# 04_LEDs.net
KiCad netlist of a schematic drawn in Altium Designer
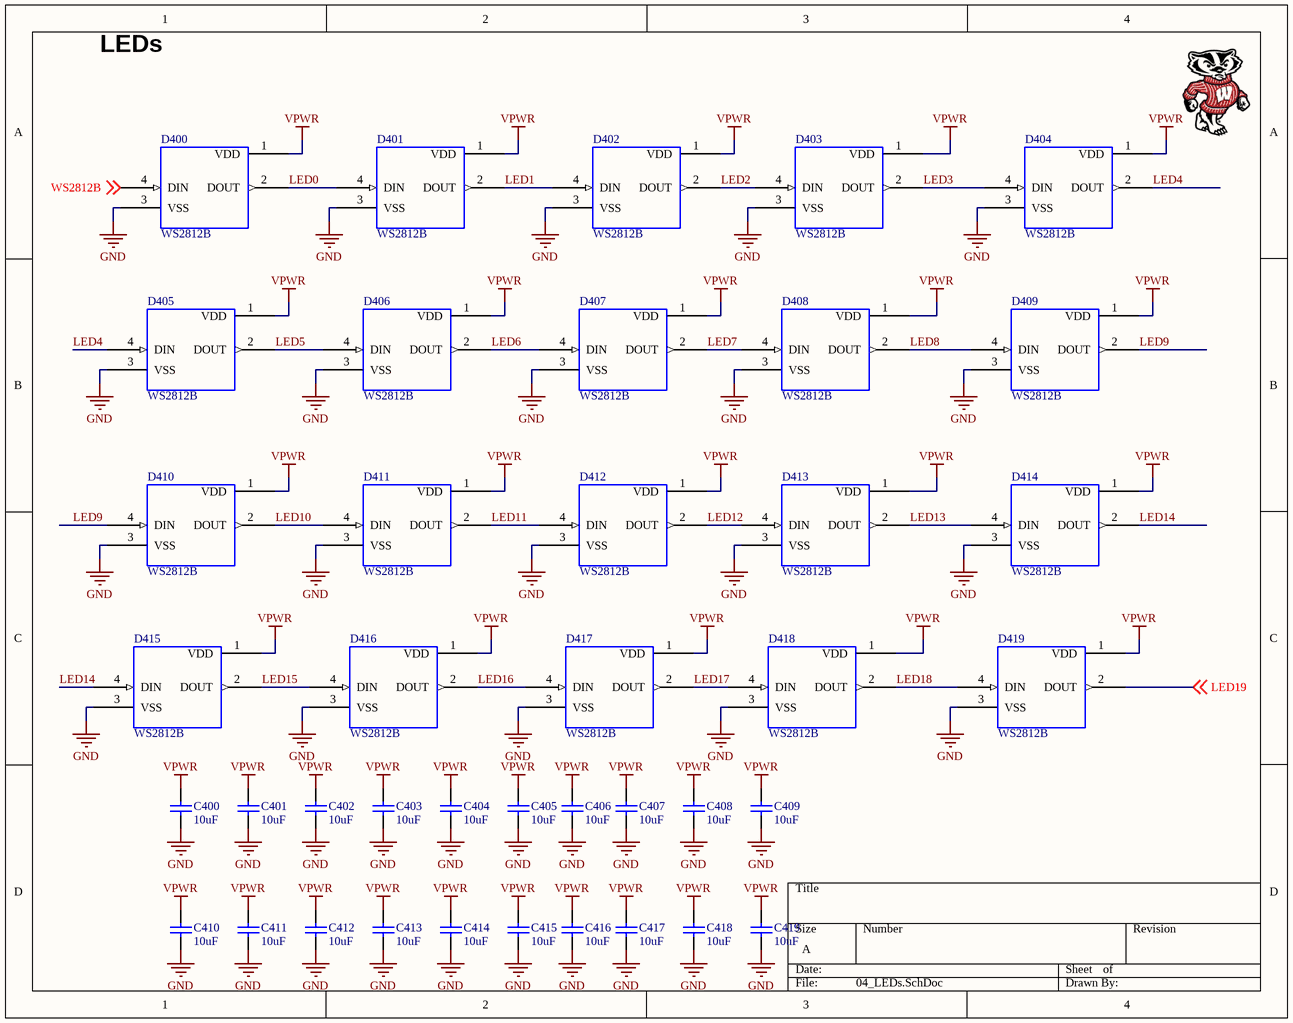
[diagram p0: 04_LEDs.SchDoc]

(export (version "E")
  (design (tool "Eeschema 10.0.6"))
  (components
    (comp (ref "C400")
      (value "10uF")
      (footprint "CAP_0805")
      (description "CAP CER 10UF 16V X7R 0805")
      (fields
        (field (name "MANUFACTURER") "Samsung")
        (field (name "MANUFACTURER PART NUMBER") "CL21A106KPCLQNC")
        (field (name "CAPACITANCE") "10uF")
      )
      (libsource (lib "ece315-2018-fall") (part "CAP_0805_U_010.00"))
    )
    (comp (ref "C401")
      (value "10uF")
      (footprint "CAP_0805")
      (description "CAP CER 10UF 16V X7R 0805")
      (fields
        (field (name "MANUFACTURER") "Samsung")
        (field (name "MANUFACTURER PART NUMBER") "CL21A106KPCLQNC")
        (field (name "CAPACITANCE") "10uF")
      )
      (libsource (lib "ece315-2018-fall") (part "CAP_0805_U_010.00"))
    )
    (comp (ref "C402")
      (value "10uF")
      (footprint "CAP_0805")
      (description "CAP CER 10UF 16V X7R 0805")
      (fields
        (field (name "MANUFACTURER") "Samsung")
        (field (name "MANUFACTURER PART NUMBER") "CL21A106KPCLQNC")
        (field (name "CAPACITANCE") "10uF")
      )
      (libsource (lib "ece315-2018-fall") (part "CAP_0805_U_010.00"))
    )
    (comp (ref "C403")
      (value "10uF")
      (footprint "CAP_0805")
      (description "CAP CER 10UF 16V X7R 0805")
      (fields
        (field (name "MANUFACTURER") "Samsung")
        (field (name "MANUFACTURER PART NUMBER") "CL21A106KPCLQNC")
        (field (name "CAPACITANCE") "10uF")
      )
      (libsource (lib "ece315-2018-fall") (part "CAP_0805_U_010.00"))
    )
    (comp (ref "C404")
      (value "10uF")
      (footprint "CAP_0805")
      (description "CAP CER 10UF 16V X7R 0805")
      (fields
        (field (name "MANUFACTURER") "Samsung")
        (field (name "MANUFACTURER PART NUMBER") "CL21A106KPCLQNC")
        (field (name "CAPACITANCE") "10uF")
      )
      (libsource (lib "ece315-2018-fall") (part "CAP_0805_U_010.00"))
    )
    (comp (ref "C405")
      (value "10uF")
      (footprint "CAP_0805")
      (description "CAP CER 10UF 16V X7R 0805")
      (fields
        (field (name "MANUFACTURER") "Samsung")
        (field (name "MANUFACTURER PART NUMBER") "CL21A106KPCLQNC")
        (field (name "CAPACITANCE") "10uF")
      )
      (libsource (lib "ece315-2018-fall") (part "CAP_0805_U_010.00"))
    )
    (comp (ref "C406")
      (value "10uF")
      (footprint "CAP_0805")
      (description "CAP CER 10UF 16V X7R 0805")
      (fields
        (field (name "MANUFACTURER") "Samsung")
        (field (name "MANUFACTURER PART NUMBER") "CL21A106KPCLQNC")
        (field (name "CAPACITANCE") "10uF")
      )
      (libsource (lib "ece315-2018-fall") (part "CAP_0805_U_010.00"))
    )
    (comp (ref "C407")
      (value "10uF")
      (footprint "CAP_0805")
      (description "CAP CER 10UF 16V X7R 0805")
      (fields
        (field (name "MANUFACTURER") "Samsung")
        (field (name "MANUFACTURER PART NUMBER") "CL21A106KPCLQNC")
        (field (name "CAPACITANCE") "10uF")
      )
      (libsource (lib "ece315-2018-fall") (part "CAP_0805_U_010.00"))
    )
    (comp (ref "C408")
      (value "10uF")
      (footprint "CAP_0805")
      (description "CAP CER 10UF 16V X7R 0805")
      (fields
        (field (name "MANUFACTURER") "Samsung")
        (field (name "MANUFACTURER PART NUMBER") "CL21A106KPCLQNC")
        (field (name "CAPACITANCE") "10uF")
      )
      (libsource (lib "ece315-2018-fall") (part "CAP_0805_U_010.00"))
    )
    (comp (ref "C409")
      (value "10uF")
      (footprint "CAP_0805")
      (description "CAP CER 10UF 16V X7R 0805")
      (fields
        (field (name "MANUFACTURER") "Samsung")
        (field (name "MANUFACTURER PART NUMBER") "CL21A106KPCLQNC")
        (field (name "CAPACITANCE") "10uF")
      )
      (libsource (lib "ece315-2018-fall") (part "CAP_0805_U_010.00"))
    )
    (comp (ref "C410")
      (value "10uF")
      (footprint "CAP_0805")
      (description "CAP CER 10UF 16V X7R 0805")
      (fields
        (field (name "MANUFACTURER") "Samsung")
        (field (name "MANUFACTURER PART NUMBER") "CL21A106KPCLQNC")
        (field (name "CAPACITANCE") "10uF")
      )
      (libsource (lib "ece315-2018-fall") (part "CAP_0805_U_010.00"))
    )
    (comp (ref "C411")
      (value "10uF")
      (footprint "CAP_0805")
      (description "CAP CER 10UF 16V X7R 0805")
      (fields
        (field (name "MANUFACTURER") "Samsung")
        (field (name "MANUFACTURER PART NUMBER") "CL21A106KPCLQNC")
        (field (name "CAPACITANCE") "10uF")
      )
      (libsource (lib "ece315-2018-fall") (part "CAP_0805_U_010.00"))
    )
    (comp (ref "C412")
      (value "10uF")
      (footprint "CAP_0805")
      (description "CAP CER 10UF 16V X7R 0805")
      (fields
        (field (name "MANUFACTURER") "Samsung")
        (field (name "MANUFACTURER PART NUMBER") "CL21A106KPCLQNC")
        (field (name "CAPACITANCE") "10uF")
      )
      (libsource (lib "ece315-2018-fall") (part "CAP_0805_U_010.00"))
    )
    (comp (ref "C413")
      (value "10uF")
      (footprint "CAP_0805")
      (description "CAP CER 10UF 16V X7R 0805")
      (fields
        (field (name "MANUFACTURER") "Samsung")
        (field (name "MANUFACTURER PART NUMBER") "CL21A106KPCLQNC")
        (field (name "CAPACITANCE") "10uF")
      )
      (libsource (lib "ece315-2018-fall") (part "CAP_0805_U_010.00"))
    )
    (comp (ref "C414")
      (value "10uF")
      (footprint "CAP_0805")
      (description "CAP CER 10UF 16V X7R 0805")
      (fields
        (field (name "MANUFACTURER") "Samsung")
        (field (name "MANUFACTURER PART NUMBER") "CL21A106KPCLQNC")
        (field (name "CAPACITANCE") "10uF")
      )
      (libsource (lib "ece315-2018-fall") (part "CAP_0805_U_010.00"))
    )
    (comp (ref "C415")
      (value "10uF")
      (footprint "CAP_0805")
      (description "CAP CER 10UF 16V X7R 0805")
      (fields
        (field (name "MANUFACTURER") "Samsung")
        (field (name "MANUFACTURER PART NUMBER") "CL21A106KPCLQNC")
        (field (name "CAPACITANCE") "10uF")
      )
      (libsource (lib "ece315-2018-fall") (part "CAP_0805_U_010.00"))
    )
    (comp (ref "C416")
      (value "10uF")
      (footprint "CAP_0805")
      (description "CAP CER 10UF 16V X7R 0805")
      (fields
        (field (name "MANUFACTURER") "Samsung")
        (field (name "MANUFACTURER PART NUMBER") "CL21A106KPCLQNC")
        (field (name "CAPACITANCE") "10uF")
      )
      (libsource (lib "ece315-2018-fall") (part "CAP_0805_U_010.00"))
    )
    (comp (ref "C417")
      (value "10uF")
      (footprint "CAP_0805")
      (description "CAP CER 10UF 16V X7R 0805")
      (fields
        (field (name "MANUFACTURER") "Samsung")
        (field (name "MANUFACTURER PART NUMBER") "CL21A106KPCLQNC")
        (field (name "CAPACITANCE") "10uF")
      )
      (libsource (lib "ece315-2018-fall") (part "CAP_0805_U_010.00"))
    )
    (comp (ref "C418")
      (value "10uF")
      (footprint "CAP_0805")
      (description "CAP CER 10UF 16V X7R 0805")
      (fields
        (field (name "MANUFACTURER") "Samsung")
        (field (name "MANUFACTURER PART NUMBER") "CL21A106KPCLQNC")
        (field (name "CAPACITANCE") "10uF")
      )
      (libsource (lib "ece315-2018-fall") (part "CAP_0805_U_010.00"))
    )
    (comp (ref "C419")
      (value "10uF")
      (footprint "CAP_0805")
      (description "CAP CER 10UF 16V X7R 0805")
      (fields
        (field (name "MANUFACTURER") "Samsung")
        (field (name "MANUFACTURER PART NUMBER") "CL21A106KPCLQNC")
        (field (name "CAPACITANCE") "10uF")
      )
      (libsource (lib "ece315-2018-fall") (part "CAP_0805_U_010.00"))
    )
    (comp (ref "D400")
      (value "WS2812B")
      (footprint "WS2812B")
      (description "LED RGB WS2812B")
      (fields (field (name "MANUFACTURER PART NUMBER") "EBAY"))
      (libsource (lib "LEDs") (part "WS2812B"))
    )
    (comp (ref "D401")
      (value "WS2812B")
      (footprint "WS2812B")
      (description "LED RGB WS2812B")
      (fields (field (name "MANUFACTURER PART NUMBER") "EBAY"))
      (libsource (lib "LEDs") (part "WS2812B"))
    )
    (comp (ref "D402")
      (value "WS2812B")
      (footprint "WS2812B")
      (description "LED RGB WS2812B")
      (fields (field (name "MANUFACTURER PART NUMBER") "EBAY"))
      (libsource (lib "LEDs") (part "WS2812B"))
    )
    (comp (ref "D403")
      (value "WS2812B")
      (footprint "WS2812B")
      (description "LED RGB WS2812B")
      (fields (field (name "MANUFACTURER PART NUMBER") "EBAY"))
      (libsource (lib "LEDs") (part "WS2812B"))
    )
    (comp (ref "D404")
      (value "WS2812B")
      (footprint "WS2812B")
      (description "LED RGB WS2812B")
      (fields (field (name "MANUFACTURER PART NUMBER") "EBAY"))
      (libsource (lib "LEDs") (part "WS2812B"))
    )
    (comp (ref "D405")
      (value "WS2812B")
      (footprint "WS2812B")
      (description "LED RGB WS2812B")
      (fields (field (name "MANUFACTURER PART NUMBER") "EBAY"))
      (libsource (lib "LEDs") (part "WS2812B"))
    )
    (comp (ref "D406")
      (value "WS2812B")
      (footprint "WS2812B")
      (description "LED RGB WS2812B")
      (fields (field (name "MANUFACTURER PART NUMBER") "EBAY"))
      (libsource (lib "LEDs") (part "WS2812B"))
    )
    (comp (ref "D407")
      (value "WS2812B")
      (footprint "WS2812B")
      (description "LED RGB WS2812B")
      (fields (field (name "MANUFACTURER PART NUMBER") "EBAY"))
      (libsource (lib "LEDs") (part "WS2812B"))
    )
    (comp (ref "D408")
      (value "WS2812B")
      (footprint "WS2812B")
      (description "LED RGB WS2812B")
      (fields (field (name "MANUFACTURER PART NUMBER") "EBAY"))
      (libsource (lib "LEDs") (part "WS2812B"))
    )
    (comp (ref "D409")
      (value "WS2812B")
      (footprint "WS2812B")
      (description "LED RGB WS2812B")
      (fields (field (name "MANUFACTURER PART NUMBER") "EBAY"))
      (libsource (lib "LEDs") (part "WS2812B"))
    )
    (comp (ref "D410")
      (value "WS2812B")
      (footprint "WS2812B")
      (description "LED RGB WS2812B")
      (fields (field (name "MANUFACTURER PART NUMBER") "EBAY"))
      (libsource (lib "LEDs") (part "WS2812B"))
    )
    (comp (ref "D411")
      (value "WS2812B")
      (footprint "WS2812B")
      (description "LED RGB WS2812B")
      (fields (field (name "MANUFACTURER PART NUMBER") "EBAY"))
      (libsource (lib "LEDs") (part "WS2812B"))
    )
    (comp (ref "D412")
      (value "WS2812B")
      (footprint "WS2812B")
      (description "LED RGB WS2812B")
      (fields (field (name "MANUFACTURER PART NUMBER") "EBAY"))
      (libsource (lib "LEDs") (part "WS2812B"))
    )
    (comp (ref "D413")
      (value "WS2812B")
      (footprint "WS2812B")
      (description "LED RGB WS2812B")
      (fields (field (name "MANUFACTURER PART NUMBER") "EBAY"))
      (libsource (lib "LEDs") (part "WS2812B"))
    )
    (comp (ref "D414")
      (value "WS2812B")
      (footprint "WS2812B")
      (description "LED RGB WS2812B")
      (fields (field (name "MANUFACTURER PART NUMBER") "EBAY"))
      (libsource (lib "LEDs") (part "WS2812B"))
    )
    (comp (ref "D415")
      (value "WS2812B")
      (footprint "WS2812B")
      (description "LED RGB WS2812B")
      (fields (field (name "MANUFACTURER PART NUMBER") "EBAY"))
      (libsource (lib "LEDs") (part "WS2812B"))
    )
    (comp (ref "D416")
      (value "WS2812B")
      (footprint "WS2812B")
      (description "LED RGB WS2812B")
      (fields (field (name "MANUFACTURER PART NUMBER") "EBAY"))
      (libsource (lib "LEDs") (part "WS2812B"))
    )
    (comp (ref "D417")
      (value "WS2812B")
      (footprint "WS2812B")
      (description "LED RGB WS2812B")
      (fields (field (name "MANUFACTURER PART NUMBER") "EBAY"))
      (libsource (lib "LEDs") (part "WS2812B"))
    )
    (comp (ref "D418")
      (value "WS2812B")
      (footprint "WS2812B")
      (description "LED RGB WS2812B")
      (fields (field (name "MANUFACTURER PART NUMBER") "EBAY"))
      (libsource (lib "LEDs") (part "WS2812B"))
    )
    (comp (ref "D419")
      (value "WS2812B")
      (footprint "WS2812B")
      (description "LED RGB WS2812B")
      (fields (field (name "MANUFACTURER PART NUMBER") "EBAY"))
      (libsource (lib "LEDs") (part "WS2812B"))
    )
  )
  (nets
    (net (code "1") (name "/LED0") (class "Default")
      (node (ref "D400") (pin "2") (pinfunction "DOUT_2") (pintype "output"))
      (node (ref "D401") (pin "4") (pinfunction "DIN_4") (pintype "input"))
    )
    (net (code "2") (name "/LED1") (class "Default")
      (node (ref "D401") (pin "2") (pinfunction "DOUT_2") (pintype "output"))
      (node (ref "D402") (pin "4") (pinfunction "DIN_4") (pintype "input"))
    )
    (net (code "3") (name "/LED2") (class "Default")
      (node (ref "D402") (pin "2") (pinfunction "DOUT_2") (pintype "output"))
      (node (ref "D403") (pin "4") (pinfunction "DIN_4") (pintype "input"))
    )
    (net (code "4") (name "/LED3") (class "Default")
      (node (ref "D403") (pin "2") (pinfunction "DOUT_2") (pintype "output"))
      (node (ref "D404") (pin "4") (pinfunction "DIN_4") (pintype "input"))
    )
    (net (code "5") (name "/LED4") (class "Default")
      (node (ref "D404") (pin "2") (pinfunction "DOUT_2") (pintype "output"))
      (node (ref "D405") (pin "4") (pinfunction "DIN_4") (pintype "input"))
    )
    (net (code "6") (name "/LED5") (class "Default")
      (node (ref "D405") (pin "2") (pinfunction "DOUT_2") (pintype "output"))
      (node (ref "D406") (pin "4") (pinfunction "DIN_4") (pintype "input"))
    )
    (net (code "7") (name "/LED6") (class "Default")
      (node (ref "D406") (pin "2") (pinfunction "DOUT_2") (pintype "output"))
      (node (ref "D407") (pin "4") (pinfunction "DIN_4") (pintype "input"))
    )
    (net (code "8") (name "/LED7") (class "Default")
      (node (ref "D407") (pin "2") (pinfunction "DOUT_2") (pintype "output"))
      (node (ref "D408") (pin "4") (pinfunction "DIN_4") (pintype "input"))
    )
    (net (code "9") (name "/LED8") (class "Default")
      (node (ref "D408") (pin "2") (pinfunction "DOUT_2") (pintype "output"))
      (node (ref "D409") (pin "4") (pinfunction "DIN_4") (pintype "input"))
    )
    (net (code "10") (name "/LED9") (class "Default")
      (node (ref "D409") (pin "2") (pinfunction "DOUT_2") (pintype "output"))
      (node (ref "D410") (pin "4") (pinfunction "DIN_4") (pintype "input"))
    )
    (net (code "11") (name "/LED10") (class "Default")
      (node (ref "D410") (pin "2") (pinfunction "DOUT_2") (pintype "output"))
      (node (ref "D411") (pin "4") (pinfunction "DIN_4") (pintype "input"))
    )
    (net (code "12") (name "/LED11") (class "Default")
      (node (ref "D411") (pin "2") (pinfunction "DOUT_2") (pintype "output"))
      (node (ref "D412") (pin "4") (pinfunction "DIN_4") (pintype "input"))
    )
    (net (code "13") (name "/LED12") (class "Default")
      (node (ref "D412") (pin "2") (pinfunction "DOUT_2") (pintype "output"))
      (node (ref "D413") (pin "4") (pinfunction "DIN_4") (pintype "input"))
    )
    (net (code "14") (name "/LED13") (class "Default")
      (node (ref "D413") (pin "2") (pinfunction "DOUT_2") (pintype "output"))
      (node (ref "D414") (pin "4") (pinfunction "DIN_4") (pintype "input"))
    )
    (net (code "15") (name "/LED14") (class "Default")
      (node (ref "D414") (pin "2") (pinfunction "DOUT_2") (pintype "output"))
      (node (ref "D415") (pin "4") (pinfunction "DIN_4") (pintype "input"))
    )
    (net (code "16") (name "/LED15") (class "Default")
      (node (ref "D415") (pin "2") (pinfunction "DOUT_2") (pintype "output"))
      (node (ref "D416") (pin "4") (pinfunction "DIN_4") (pintype "input"))
    )
    (net (code "17") (name "/LED16") (class "Default")
      (node (ref "D416") (pin "2") (pinfunction "DOUT_2") (pintype "output"))
      (node (ref "D417") (pin "4") (pinfunction "DIN_4") (pintype "input"))
    )
    (net (code "18") (name "/LED17") (class "Default")
      (node (ref "D417") (pin "2") (pinfunction "DOUT_2") (pintype "output"))
      (node (ref "D418") (pin "4") (pinfunction "DIN_4") (pintype "input"))
    )
    (net (code "19") (name "/LED18") (class "Default")
      (node (ref "D418") (pin "2") (pinfunction "DOUT_2") (pintype "output"))
      (node (ref "D419") (pin "4") (pinfunction "DIN_4") (pintype "input"))
    )
    (net (code "20") (name "GND") (class "Default")
      (node (ref "C400") (pin "1") (pinfunction "1_1") (pintype "passive"))
      (node (ref "C401") (pin "1") (pinfunction "1_1") (pintype "passive"))
      (node (ref "C402") (pin "1") (pinfunction "1_1") (pintype "passive"))
      (node (ref "C403") (pin "1") (pinfunction "1_1") (pintype "passive"))
      (node (ref "C404") (pin "1") (pinfunction "1_1") (pintype "passive"))
      (node (ref "C405") (pin "1") (pinfunction "1_1") (pintype "passive"))
      (node (ref "C406") (pin "1") (pinfunction "1_1") (pintype "passive"))
      (node (ref "C407") (pin "1") (pinfunction "1_1") (pintype "passive"))
      (node (ref "C408") (pin "1") (pinfunction "1_1") (pintype "passive"))
      (node (ref "C409") (pin "1") (pinfunction "1_1") (pintype "passive"))
      (node (ref "C410") (pin "1") (pinfunction "1_1") (pintype "passive"))
      (node (ref "C411") (pin "1") (pinfunction "1_1") (pintype "passive"))
      (node (ref "C412") (pin "1") (pinfunction "1_1") (pintype "passive"))
      (node (ref "C413") (pin "1") (pinfunction "1_1") (pintype "passive"))
      (node (ref "C414") (pin "1") (pinfunction "1_1") (pintype "passive"))
      (node (ref "C415") (pin "1") (pinfunction "1_1") (pintype "passive"))
      (node (ref "C416") (pin "1") (pinfunction "1_1") (pintype "passive"))
      (node (ref "C417") (pin "1") (pinfunction "1_1") (pintype "passive"))
      (node (ref "C418") (pin "1") (pinfunction "1_1") (pintype "passive"))
      (node (ref "C419") (pin "1") (pinfunction "1_1") (pintype "passive"))
      (node (ref "D400") (pin "3") (pinfunction "VSS_3") (pintype "power_in"))
      (node (ref "D401") (pin "3") (pinfunction "VSS_3") (pintype "power_in"))
      (node (ref "D402") (pin "3") (pinfunction "VSS_3") (pintype "power_in"))
      (node (ref "D403") (pin "3") (pinfunction "VSS_3") (pintype "power_in"))
      (node (ref "D404") (pin "3") (pinfunction "VSS_3") (pintype "power_in"))
      (node (ref "D405") (pin "3") (pinfunction "VSS_3") (pintype "power_in"))
      (node (ref "D406") (pin "3") (pinfunction "VSS_3") (pintype "power_in"))
      (node (ref "D407") (pin "3") (pinfunction "VSS_3") (pintype "power_in"))
      (node (ref "D408") (pin "3") (pinfunction "VSS_3") (pintype "power_in"))
      (node (ref "D409") (pin "3") (pinfunction "VSS_3") (pintype "power_in"))
      (node (ref "D410") (pin "3") (pinfunction "VSS_3") (pintype "power_in"))
      (node (ref "D411") (pin "3") (pinfunction "VSS_3") (pintype "power_in"))
      (node (ref "D412") (pin "3") (pinfunction "VSS_3") (pintype "power_in"))
      (node (ref "D413") (pin "3") (pinfunction "VSS_3") (pintype "power_in"))
      (node (ref "D414") (pin "3") (pinfunction "VSS_3") (pintype "power_in"))
      (node (ref "D415") (pin "3") (pinfunction "VSS_3") (pintype "power_in"))
      (node (ref "D416") (pin "3") (pinfunction "VSS_3") (pintype "power_in"))
      (node (ref "D417") (pin "3") (pinfunction "VSS_3") (pintype "power_in"))
      (node (ref "D418") (pin "3") (pinfunction "VSS_3") (pintype "power_in"))
      (node (ref "D419") (pin "3") (pinfunction "VSS_3") (pintype "power_in"))
    )
    (net (code "21") (name "LED19") (class "Default")
      (node (ref "D419") (pin "2") (pinfunction "DOUT_2") (pintype "output"))
    )
    (net (code "22") (name "VPWR") (class "Default")
      (node (ref "C400") (pin "2") (pinfunction "2_2") (pintype "passive"))
      (node (ref "C401") (pin "2") (pinfunction "2_2") (pintype "passive"))
      (node (ref "C402") (pin "2") (pinfunction "2_2") (pintype "passive"))
      (node (ref "C403") (pin "2") (pinfunction "2_2") (pintype "passive"))
      (node (ref "C404") (pin "2") (pinfunction "2_2") (pintype "passive"))
      (node (ref "C405") (pin "2") (pinfunction "2_2") (pintype "passive"))
      (node (ref "C406") (pin "2") (pinfunction "2_2") (pintype "passive"))
      (node (ref "C407") (pin "2") (pinfunction "2_2") (pintype "passive"))
      (node (ref "C408") (pin "2") (pinfunction "2_2") (pintype "passive"))
      (node (ref "C409") (pin "2") (pinfunction "2_2") (pintype "passive"))
      (node (ref "C410") (pin "2") (pinfunction "2_2") (pintype "passive"))
      (node (ref "C411") (pin "2") (pinfunction "2_2") (pintype "passive"))
      (node (ref "C412") (pin "2") (pinfunction "2_2") (pintype "passive"))
      (node (ref "C413") (pin "2") (pinfunction "2_2") (pintype "passive"))
      (node (ref "C414") (pin "2") (pinfunction "2_2") (pintype "passive"))
      (node (ref "C415") (pin "2") (pinfunction "2_2") (pintype "passive"))
      (node (ref "C416") (pin "2") (pinfunction "2_2") (pintype "passive"))
      (node (ref "C417") (pin "2") (pinfunction "2_2") (pintype "passive"))
      (node (ref "C418") (pin "2") (pinfunction "2_2") (pintype "passive"))
      (node (ref "C419") (pin "2") (pinfunction "2_2") (pintype "passive"))
      (node (ref "D400") (pin "1") (pinfunction "VDD_1") (pintype "power_in"))
      (node (ref "D401") (pin "1") (pinfunction "VDD_1") (pintype "power_in"))
      (node (ref "D402") (pin "1") (pinfunction "VDD_1") (pintype "power_in"))
      (node (ref "D403") (pin "1") (pinfunction "VDD_1") (pintype "power_in"))
      (node (ref "D404") (pin "1") (pinfunction "VDD_1") (pintype "power_in"))
      (node (ref "D405") (pin "1") (pinfunction "VDD_1") (pintype "power_in"))
      (node (ref "D406") (pin "1") (pinfunction "VDD_1") (pintype "power_in"))
      (node (ref "D407") (pin "1") (pinfunction "VDD_1") (pintype "power_in"))
      (node (ref "D408") (pin "1") (pinfunction "VDD_1") (pintype "power_in"))
      (node (ref "D409") (pin "1") (pinfunction "VDD_1") (pintype "power_in"))
      (node (ref "D410") (pin "1") (pinfunction "VDD_1") (pintype "power_in"))
      (node (ref "D411") (pin "1") (pinfunction "VDD_1") (pintype "power_in"))
      (node (ref "D412") (pin "1") (pinfunction "VDD_1") (pintype "power_in"))
      (node (ref "D413") (pin "1") (pinfunction "VDD_1") (pintype "power_in"))
      (node (ref "D414") (pin "1") (pinfunction "VDD_1") (pintype "power_in"))
      (node (ref "D415") (pin "1") (pinfunction "VDD_1") (pintype "power_in"))
      (node (ref "D416") (pin "1") (pinfunction "VDD_1") (pintype "power_in"))
      (node (ref "D417") (pin "1") (pinfunction "VDD_1") (pintype "power_in"))
      (node (ref "D418") (pin "1") (pinfunction "VDD_1") (pintype "power_in"))
      (node (ref "D419") (pin "1") (pinfunction "VDD_1") (pintype "power_in"))
    )
    (net (code "23") (name "WS2812B") (class "Default")
      (node (ref "D400") (pin "4") (pinfunction "DIN_4") (pintype "input"))
    )
  )
)
